# LEDs.net
KiCad netlist of a schematic drawn in Altium Designer
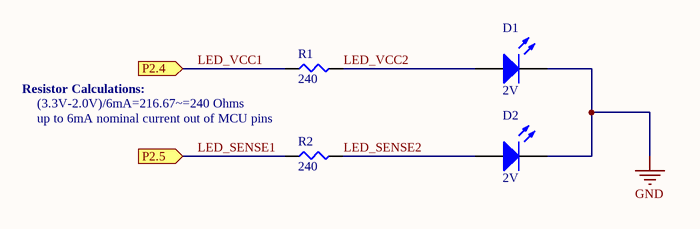
[diagram p0: LEDs.SchDoc]

(export (version "E")
  (design (tool "Eeschema 10.0.6"))
  (components
    (comp (ref "D1")
      (value "2V")
      (footprint "0805_A")
      (description "SMD mono-color Chip LED, WL-SMCW, Bright Green")
      (fields (field (name "PARTNUMBER") "150080VS75000") (field (name "MANUFACTURER") "Wuerth Elektronik"))
      (libsource (lib "Altium Content Vault") (part "WE-LED_K1A2-2"))
    )
    (comp (ref "D2")
      (value "2V")
      (footprint "0805_A")
      (description "SMD mono-color Chip LED, WL-SMCW, Bright Green")
      (fields (field (name "PARTNUMBER") "150080VS75000") (field (name "MANUFACTURER") "Wuerth Elektronik"))
      (libsource (lib "Altium Content Vault") (part "WE-LED_K1A2-2"))
    )
    (comp (ref "R1")
      (value "240")
      (footprint "SMD-0805-RES")
      (description "RES SMD 240 OHM 1% 1/8W 0805")
      (fields (field (name "PART NUMBER") "ERJ-6ENF2400V") (field (name "DIGI-KEY PART NUMBER") "P240CCT-ND"))
      (libsource (lib "Panasonic_resistor_0805") (part "ERJ-6ENF2400V"))
    )
    (comp (ref "R2")
      (value "240")
      (footprint "SMD-0805-RES")
      (description "RES SMD 240 OHM 1% 1/8W 0805")
      (fields (field (name "PART NUMBER") "ERJ-6ENF2400V") (field (name "DIGI-KEY PART NUMBER") "P240CCT-ND"))
      (libsource (lib "Panasonic_resistor_0805") (part "ERJ-6ENF2400V"))
    )
  )
  (nets
    (net (code "1") (name "/LED_SENSE1") (class "Default")
      (node (ref "R2") (pin "1") (pinfunction "1_1") (pintype "passive"))
    )
    (net (code "2") (name "/LED_SENSE2") (class "Default")
      (node (ref "D2") (pin "2") (pinfunction "A_2") (pintype "passive"))
      (node (ref "R2") (pin "2") (pinfunction "2_2") (pintype "passive"))
    )
    (net (code "3") (name "/LED_VCC1") (class "Default")
      (node (ref "R1") (pin "1") (pinfunction "1_1") (pintype "passive"))
    )
    (net (code "4") (name "/LED_VCC2") (class "Default")
      (node (ref "D1") (pin "2") (pinfunction "A_2") (pintype "passive"))
      (node (ref "R1") (pin "2") (pinfunction "2_2") (pintype "passive"))
    )
    (net (code "5") (name "GND") (class "Default")
      (node (ref "D1") (pin "1") (pinfunction "K_1") (pintype "passive"))
      (node (ref "D2") (pin "1") (pinfunction "K_1") (pintype "passive"))
    )
  )
)
